# 05_MICROCONTROLLER.net
KiCad netlist of a schematic drawn in Altium Designer
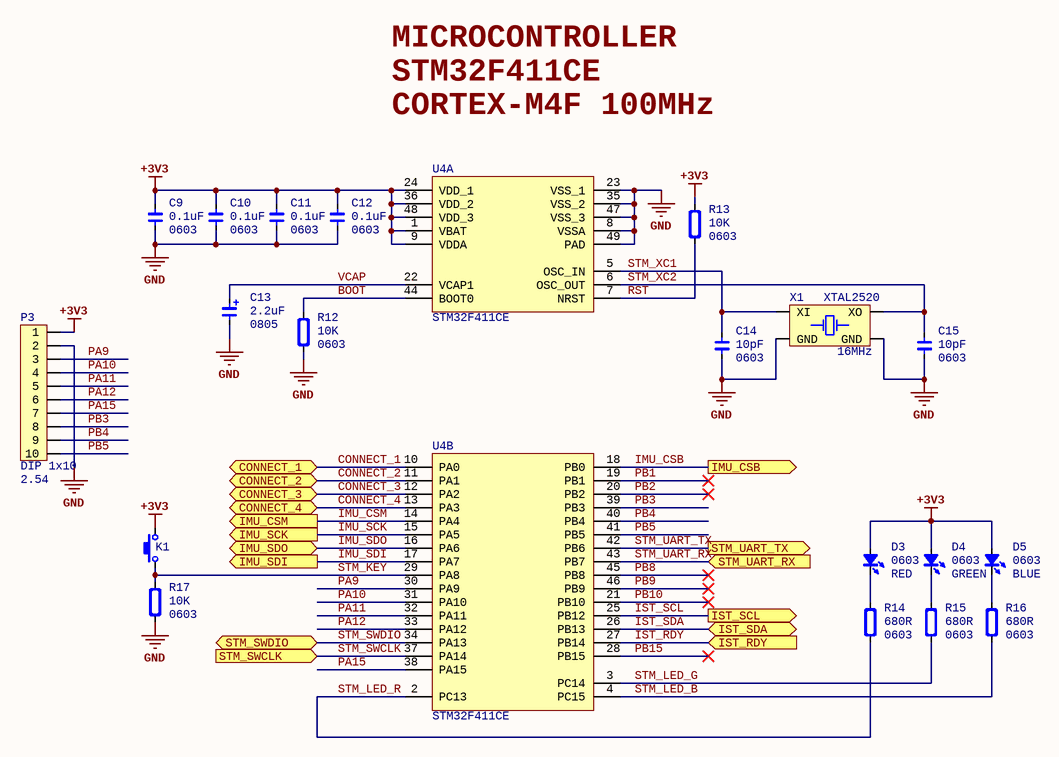
[diagram p0: [05] MICROCONTROLLER.SchDoc]

(export (version "E")
  (design (tool "Eeschema 10.0.6"))
  (components
    (comp (ref "C9")
      (value "0.1uF")
      (footprint "PCB_PassiveCap:CAP_0603")
      (description "Capacitor")
      (fields (field (name "TYPE") "0603"))
      (libsource (lib "SCH_Passive") (part "Cap_0603"))
    )
    (comp (ref "C10")
      (value "0.1uF")
      (footprint "PCB_PassiveCap:CAP_0603")
      (description "Capacitor")
      (fields (field (name "TYPE") "0603"))
      (libsource (lib "SCH_Passive") (part "Cap_0603"))
    )
    (comp (ref "C11")
      (value "0.1uF")
      (footprint "PCB_PassiveCap:CAP_0603")
      (description "Capacitor")
      (fields (field (name "TYPE") "0603"))
      (libsource (lib "SCH_Passive") (part "Cap_0603"))
    )
    (comp (ref "C12")
      (value "0.1uF")
      (footprint "PCB_PassiveCap:CAP_0603")
      (description "Capacitor")
      (fields (field (name "TYPE") "0603"))
      (libsource (lib "SCH_Passive") (part "Cap_0603"))
    )
    (comp (ref "C13")
      (value "2.2uF")
      (footprint "PCB_PassiveCap:CAP_TAN_P0805")
      (description "Capacitor Tantalum")
      (fields (field (name "TYPE") "0805"))
      (libsource (lib "SCH_Passive") (part "Cap_Tan_0805"))
    )
    (comp (ref "C14")
      (value "10pF")
      (footprint "PCB_PassiveCap:CAP_0603")
      (description "Capacitor")
      (fields (field (name "TYPE") "0603"))
      (libsource (lib "SCH_Passive") (part "Cap_0603"))
    )
    (comp (ref "C15")
      (value "10pF")
      (footprint "PCB_PassiveCap:CAP_0603")
      (description "Capacitor")
      (fields (field (name "TYPE") "0603"))
      (libsource (lib "SCH_Passive") (part "Cap_0603"))
    )
    (comp (ref "D3")
      (value "RED")
      (footprint "PCB_ActiveLED:LED_0603_RED")
      (description "LED")
      (fields (field (name "TYPE") "0603"))
      (libsource (lib "SCH_Active") (part "LED_0603"))
    )
    (comp (ref "D4")
      (value "GREEN")
      (footprint "PCB_ActiveLED:LED_0603_GREEN")
      (description "LED")
      (fields (field (name "TYPE") "0603"))
      (libsource (lib "SCH_Active") (part "LED_0603"))
    )
    (comp (ref "D5")
      (value "BLUE")
      (footprint "PCB_ActiveLED:LED_0603_BLUE")
      (description "LED")
      (fields (field (name "TYPE") "0603"))
      (libsource (lib "SCH_Active") (part "LED_0603"))
    )
    (comp (ref "K1")
      (value "ButtonTACT")
      (footprint "PCB_Switch:ButtonTACT_3x4x2_180H")
      (description "Button")
      (libsource (lib "SCH_Switch") (part "ButtonTACT_3x4x2_180"))
    )
    (comp (ref "P3")
      (value "2.54")
      (footprint "PCB_ConnectorHDR:HDR1X10_2.54_180")
      (description "Header")
      (fields (field (name "TYPE") "DIP 1x10") (field (name "Comment") "DIP 1x10"))
      (libsource (lib "SCH_ConnectorHDR") (part "HDR1x10_2.54T"))
    )
    (comp (ref "R12")
      (value "10K")
      (footprint "PCB_PassiveRes:RES_0603")
      (description "Resistor")
      (fields (field (name "TYPE") "0603"))
      (libsource (lib "SCH_Passive") (part "Res_0603"))
    )
    (comp (ref "R13")
      (value "10K")
      (footprint "PCB_PassiveRes:RES_0603")
      (description "Resistor")
      (fields (field (name "TYPE") "0603"))
      (libsource (lib "SCH_Passive") (part "Res_0603"))
    )
    (comp (ref "R14")
      (value "680R")
      (footprint "PCB_PassiveRes:RES_0603")
      (description "Resistor")
      (fields (field (name "TYPE") "0603"))
      (libsource (lib "SCH_Passive") (part "Res_0603"))
    )
    (comp (ref "R15")
      (value "680R")
      (footprint "PCB_PassiveRes:RES_0603")
      (description "Resistor")
      (fields (field (name "TYPE") "0603"))
      (libsource (lib "SCH_Passive") (part "Res_0603"))
    )
    (comp (ref "R16")
      (value "680R")
      (footprint "PCB_PassiveRes:RES_0603")
      (description "Resistor")
      (fields (field (name "TYPE") "0603"))
      (libsource (lib "SCH_Passive") (part "Res_0603"))
    )
    (comp (ref "R17")
      (value "10K")
      (footprint "PCB_PassiveRes:RES_0603")
      (description "Resistor")
      (fields (field (name "TYPE") "0603"))
      (libsource (lib "SCH_Passive") (part "Res_0603"))
    )
    (comp (ref "U4")
      (value "STM32F411CE")
      (footprint "PCB_IntegratedCircuit:QFN_P0.5_48")
      (description "MCU")
      (libsource (lib "SCH_IntegratedCircuit") (part "STM32F4x1C"))
    )
    (comp (ref "X1")
      (value "16MHz")
      (footprint "PCB_Oscillator:XT_2520_4")
      (description "Crystal Oscillator")
      (fields (field (name "TYPE") "XTAL2520"))
      (libsource (lib "SCH_Oscillator") (part "XTAL_2520_4P"))
    )
  )
  (nets
    (net (code "1") (name "+3V3") (class "Default")
      (node (ref "C10") (pin "2") (pinfunction "2_2") (pintype "passive"))
      (node (ref "C11") (pin "2") (pinfunction "2_2") (pintype "passive"))
      (node (ref "C12") (pin "2") (pinfunction "2_2") (pintype "passive"))
      (node (ref "C9") (pin "2") (pinfunction "2_2") (pintype "passive"))
      (node (ref "D3") (pin "1") (pinfunction "A_1") (pintype "passive"))
      (node (ref "D4") (pin "1") (pinfunction "A_1") (pintype "passive"))
      (node (ref "D5") (pin "1") (pinfunction "A_1") (pintype "passive"))
      (node (ref "K1") (pin "2") (pinfunction "2_2") (pintype "passive"))
      (node (ref "P3") (pin "1") (pinfunction "1_1") (pintype "passive"))
      (node (ref "R13") (pin "2") (pinfunction "2_2") (pintype "passive"))
      (node (ref "U4") (pin "1") (pinfunction "VBAT_1") (pintype "passive"))
      (node (ref "U4") (pin "24") (pinfunction "VDD_1_24") (pintype "passive"))
      (node (ref "U4") (pin "36") (pinfunction "VDD_2_36") (pintype "passive"))
      (node (ref "U4") (pin "48") (pinfunction "VDD_3_48") (pintype "passive"))
      (node (ref "U4") (pin "9") (pinfunction "VDDA_9") (pintype "passive"))
    )
    (net (code "2") (name "/BOOT") (class "Default")
      (node (ref "R12") (pin "2") (pinfunction "2_2") (pintype "passive"))
      (node (ref "U4") (pin "44") (pinfunction "BOOT0_44") (pintype "passive"))
    )
    (net (code "3") (name "/CONNECT_1") (class "Default")
      (node (ref "U4") (pin "10") (pinfunction "PA0_10") (pintype "passive"))
    )
    (net (code "4") (name "/CONNECT_2") (class "Default")
      (node (ref "U4") (pin "11") (pinfunction "PA1_11") (pintype "passive"))
    )
    (net (code "5") (name "/CONNECT_3") (class "Default")
      (node (ref "U4") (pin "12") (pinfunction "PA2_12") (pintype "passive"))
    )
    (net (code "6") (name "/CONNECT_4") (class "Default")
      (node (ref "U4") (pin "13") (pinfunction "PA3_13") (pintype "passive"))
    )
    (net (code "7") (name "/IMU_CSB") (class "Default")
      (node (ref "U4") (pin "18") (pinfunction "PB0_18") (pintype "passive"))
    )
    (net (code "8") (name "/IMU_CSM") (class "Default")
      (node (ref "U4") (pin "14") (pinfunction "PA4_14") (pintype "passive"))
    )
    (net (code "9") (name "/IMU_SCK") (class "Default")
      (node (ref "U4") (pin "15") (pinfunction "PA5_15") (pintype "passive"))
    )
    (net (code "10") (name "/IMU_SDI") (class "Default")
      (node (ref "U4") (pin "17") (pinfunction "PA7_17") (pintype "passive"))
    )
    (net (code "11") (name "/IMU_SDO") (class "Default")
      (node (ref "U4") (pin "16") (pinfunction "PA6_16") (pintype "passive"))
    )
    (net (code "12") (name "/IST_RDY") (class "Default")
      (node (ref "U4") (pin "27") (pinfunction "PB14_27") (pintype "passive"))
    )
    (net (code "13") (name "/IST_SCL") (class "Default")
      (node (ref "U4") (pin "25") (pinfunction "PB12_25") (pintype "passive"))
    )
    (net (code "14") (name "/IST_SDA") (class "Default")
      (node (ref "U4") (pin "26") (pinfunction "PB13_26") (pintype "passive"))
    )
    (net (code "15") (name "/PA9") (class "Default")
      (node (ref "P3") (pin "3") (pinfunction "3_3") (pintype "passive"))
      (node (ref "U4") (pin "30") (pinfunction "PA9_30") (pintype "passive"))
    )
    (net (code "16") (name "/PA10") (class "Default")
      (node (ref "P3") (pin "4") (pinfunction "4_4") (pintype "passive"))
      (node (ref "U4") (pin "31") (pinfunction "PA10_31") (pintype "passive"))
    )
    (net (code "17") (name "/PA11") (class "Default")
      (node (ref "P3") (pin "5") (pinfunction "5_5") (pintype "passive"))
      (node (ref "U4") (pin "32") (pinfunction "PA11_32") (pintype "passive"))
    )
    (net (code "18") (name "/PA12") (class "Default")
      (node (ref "P3") (pin "6") (pinfunction "6_6") (pintype "passive"))
      (node (ref "U4") (pin "33") (pinfunction "PA12_33") (pintype "passive"))
    )
    (net (code "19") (name "/PA15") (class "Default")
      (node (ref "P3") (pin "7") (pinfunction "7_7") (pintype "passive"))
      (node (ref "U4") (pin "38") (pinfunction "PA15_38") (pintype "passive"))
    )
    (net (code "20") (name "/PB1") (class "Default")
      (node (ref "U4") (pin "19") (pinfunction "PB1_19") (pintype "passive+no_connect"))
    )
    (net (code "21") (name "/PB2") (class "Default")
      (node (ref "U4") (pin "20") (pinfunction "PB2_20") (pintype "passive+no_connect"))
    )
    (net (code "22") (name "/PB3") (class "Default")
      (node (ref "P3") (pin "8") (pinfunction "8_8") (pintype "passive"))
      (node (ref "U4") (pin "39") (pinfunction "PB3_39") (pintype "passive"))
    )
    (net (code "23") (name "/PB4") (class "Default")
      (node (ref "P3") (pin "9") (pinfunction "9_9") (pintype "passive"))
      (node (ref "U4") (pin "40") (pinfunction "PB4_40") (pintype "passive"))
    )
    (net (code "24") (name "/PB5") (class "Default")
      (node (ref "P3") (pin "10") (pinfunction "10_10") (pintype "passive"))
      (node (ref "U4") (pin "41") (pinfunction "PB5_41") (pintype "passive"))
    )
    (net (code "25") (name "/PB8") (class "Default")
      (node (ref "U4") (pin "45") (pinfunction "PB8_45") (pintype "passive+no_connect"))
    )
    (net (code "26") (name "/PB9") (class "Default")
      (node (ref "U4") (pin "46") (pinfunction "PB9_46") (pintype "passive+no_connect"))
    )
    (net (code "27") (name "/PB10") (class "Default")
      (node (ref "U4") (pin "21") (pinfunction "PB10_21") (pintype "passive+no_connect"))
    )
    (net (code "28") (name "/PB15") (class "Default")
      (node (ref "U4") (pin "28") (pinfunction "PB15_28") (pintype "passive+no_connect"))
    )
    (net (code "29") (name "/RST") (class "Default")
      (node (ref "R13") (pin "1") (pinfunction "1_1") (pintype "passive"))
      (node (ref "U4") (pin "7") (pinfunction "NRST_7") (pintype "passive"))
    )
    (net (code "30") (name "/STM_KEY") (class "Default")
      (node (ref "K1") (pin "1") (pinfunction "1_1") (pintype "passive"))
      (node (ref "R17") (pin "2") (pinfunction "2_2") (pintype "passive"))
      (node (ref "U4") (pin "29") (pinfunction "PA8_29") (pintype "passive"))
    )
    (net (code "31") (name "/STM_LED_B") (class "Default")
      (node (ref "R16") (pin "1") (pinfunction "1_1") (pintype "passive"))
      (node (ref "U4") (pin "4") (pinfunction "PC15_4") (pintype "passive"))
    )
    (net (code "32") (name "/STM_LED_G") (class "Default")
      (node (ref "R15") (pin "1") (pinfunction "1_1") (pintype "passive"))
      (node (ref "U4") (pin "3") (pinfunction "PC14_3") (pintype "passive"))
    )
    (net (code "33") (name "/STM_LED_R") (class "Default")
      (node (ref "R14") (pin "1") (pinfunction "1_1") (pintype "passive"))
      (node (ref "U4") (pin "2") (pinfunction "PC13_2") (pintype "passive"))
    )
    (net (code "34") (name "/STM_SWCLK") (class "Default")
      (node (ref "U4") (pin "37") (pinfunction "PA14_37") (pintype "passive"))
    )
    (net (code "35") (name "/STM_SWDIO") (class "Default")
      (node (ref "U4") (pin "34") (pinfunction "PA13_34") (pintype "passive"))
    )
    (net (code "36") (name "/STM_UART_RX") (class "Default")
      (node (ref "U4") (pin "43") (pinfunction "PB7_43") (pintype "passive"))
    )
    (net (code "37") (name "/STM_UART_TX") (class "Default")
      (node (ref "U4") (pin "42") (pinfunction "PB6_42") (pintype "passive"))
    )
    (net (code "38") (name "/STM_XC1") (class "Default")
      (node (ref "C14") (pin "2") (pinfunction "2_2") (pintype "passive"))
      (node (ref "U4") (pin "5") (pinfunction "OSC_IN_5") (pintype "passive"))
      (node (ref "X1") (pin "1") (pinfunction "XI_1") (pintype "passive"))
    )
    (net (code "39") (name "/STM_XC2") (class "Default")
      (node (ref "C15") (pin "2") (pinfunction "2_2") (pintype "passive"))
      (node (ref "U4") (pin "6") (pinfunction "OSC_OUT_6") (pintype "passive"))
      (node (ref "X1") (pin "3") (pinfunction "XO_3") (pintype "passive"))
    )
    (net (code "40") (name "/VCAP") (class "Default")
      (node (ref "C13") (pin "1") (pinfunction "1_1") (pintype "passive"))
      (node (ref "U4") (pin "22") (pinfunction "VCAP1_22") (pintype "passive"))
    )
    (net (code "41") (name "GND") (class "Default")
      (node (ref "C10") (pin "1") (pinfunction "1_1") (pintype "passive"))
      (node (ref "C11") (pin "1") (pinfunction "1_1") (pintype "passive"))
      (node (ref "C12") (pin "1") (pinfunction "1_1") (pintype "passive"))
      (node (ref "C13") (pin "2") (pinfunction "2_2") (pintype "passive"))
      (node (ref "C14") (pin "1") (pinfunction "1_1") (pintype "passive"))
      (node (ref "C15") (pin "1") (pinfunction "1_1") (pintype "passive"))
      (node (ref "C9") (pin "1") (pinfunction "1_1") (pintype "passive"))
      (node (ref "P3") (pin "2") (pinfunction "2_2") (pintype "passive"))
      (node (ref "R12") (pin "1") (pinfunction "1_1") (pintype "passive"))
      (node (ref "R17") (pin "1") (pinfunction "1_1") (pintype "passive"))
      (node (ref "U4") (pin "23") (pinfunction "VSS_1_23") (pintype "passive"))
      (node (ref "U4") (pin "35") (pinfunction "VSS_2_35") (pintype "passive"))
      (node (ref "U4") (pin "47") (pinfunction "VSS_3_47") (pintype "passive"))
      (node (ref "U4") (pin "49") (pinfunction "PAD_49") (pintype "passive"))
      (node (ref "U4") (pin "8") (pinfunction "VSSA_8") (pintype "passive"))
      (node (ref "X1") (pin "2") (pinfunction "GND_2") (pintype "passive"))
      (node (ref "X1") (pin "4") (pinfunction "GND_4") (pintype "passive"))
    )
    (net (code "42") (name "Net-(D3-K)") (class "Default")
      (node (ref "D3") (pin "2") (pinfunction "K_2") (pintype "passive"))
      (node (ref "R14") (pin "2") (pinfunction "2_2") (pintype "passive"))
    )
    (net (code "43") (name "Net-(D4-K)") (class "Default")
      (node (ref "D4") (pin "2") (pinfunction "K_2") (pintype "passive"))
      (node (ref "R15") (pin "2") (pinfunction "2_2") (pintype "passive"))
    )
    (net (code "44") (name "Net-(D5-K)") (class "Default")
      (node (ref "D5") (pin "2") (pinfunction "K_2") (pintype "passive"))
      (node (ref "R16") (pin "2") (pinfunction "2_2") (pintype "passive"))
    )
  )
)
